# RasPi_Hat_Temp.net
KiCad netlist of a schematic drawn in Altium Designer
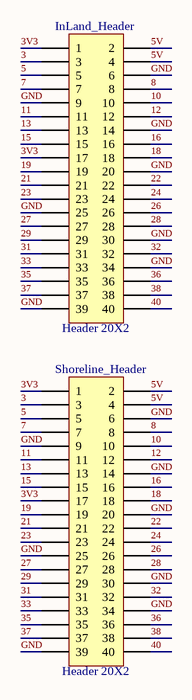
[diagram p0: RasPi_Hat_Temp.SchDoc]

(export (version "E")
  (design (tool "Eeschema 10.0.6"))
  (components
    (comp (ref "InLand_Header")
      (value "Header 20X2")
      (footprint "HDR2X20")
      (description "Header, 20-Pin, Dual row")
      (fields (field (name "PUBLISHER") "Altium Limited"))
      (libsource (lib "Miscellaneous Connectors") (part "Header 20X2"))
    )
    (comp (ref "Shoreline_Header")
      (value "Header 20X2")
      (footprint "HDR2X20")
      (description "Header, 20-Pin, Dual row")
      (fields (field (name "PUBLISHER") "Altium Limited"))
      (libsource (lib "Miscellaneous Connectors") (part "Header 20X2"))
    )
  )
  (nets
    (net (code "1") (name "/3") (class "Default")
      (node (ref "InLand_Header") (pin "3") (pinfunction "3_3") (pintype "passive"))
      (node (ref "Shoreline_Header") (pin "3") (pinfunction "3_3") (pintype "passive"))
    )
    (net (code "2") (name "/3V3") (class "Default")
      (node (ref "InLand_Header") (pin "1") (pinfunction "1_1") (pintype "passive"))
      (node (ref "InLand_Header") (pin "17") (pinfunction "17_17") (pintype "passive"))
      (node (ref "Shoreline_Header") (pin "1") (pinfunction "1_1") (pintype "passive"))
      (node (ref "Shoreline_Header") (pin "17") (pinfunction "17_17") (pintype "passive"))
    )
    (net (code "3") (name "/5") (class "Default")
      (node (ref "InLand_Header") (pin "5") (pinfunction "5_5") (pintype "passive"))
      (node (ref "Shoreline_Header") (pin "5") (pinfunction "5_5") (pintype "passive"))
    )
    (net (code "4") (name "/5V") (class "Default")
      (node (ref "InLand_Header") (pin "2") (pinfunction "2_2") (pintype "passive"))
      (node (ref "InLand_Header") (pin "4") (pinfunction "4_4") (pintype "passive"))
      (node (ref "Shoreline_Header") (pin "2") (pinfunction "2_2") (pintype "passive"))
      (node (ref "Shoreline_Header") (pin "4") (pinfunction "4_4") (pintype "passive"))
    )
    (net (code "5") (name "/7") (class "Default")
      (node (ref "InLand_Header") (pin "7") (pinfunction "7_7") (pintype "passive"))
      (node (ref "Shoreline_Header") (pin "7") (pinfunction "7_7") (pintype "passive"))
    )
    (net (code "6") (name "/8") (class "Default")
      (node (ref "InLand_Header") (pin "8") (pinfunction "8_8") (pintype "passive"))
      (node (ref "Shoreline_Header") (pin "8") (pinfunction "8_8") (pintype "passive"))
    )
    (net (code "7") (name "/10") (class "Default")
      (node (ref "InLand_Header") (pin "10") (pinfunction "10_10") (pintype "passive"))
      (node (ref "Shoreline_Header") (pin "10") (pinfunction "10_10") (pintype "passive"))
    )
    (net (code "8") (name "/11") (class "Default")
      (node (ref "InLand_Header") (pin "11") (pinfunction "11_11") (pintype "passive"))
      (node (ref "Shoreline_Header") (pin "11") (pinfunction "11_11") (pintype "passive"))
    )
    (net (code "9") (name "/12") (class "Default")
      (node (ref "InLand_Header") (pin "12") (pinfunction "12_12") (pintype "passive"))
      (node (ref "Shoreline_Header") (pin "12") (pinfunction "12_12") (pintype "passive"))
    )
    (net (code "10") (name "/13") (class "Default")
      (node (ref "InLand_Header") (pin "13") (pinfunction "13_13") (pintype "passive"))
      (node (ref "Shoreline_Header") (pin "13") (pinfunction "13_13") (pintype "passive"))
    )
    (net (code "11") (name "/15") (class "Default")
      (node (ref "InLand_Header") (pin "15") (pinfunction "15_15") (pintype "passive"))
      (node (ref "Shoreline_Header") (pin "15") (pinfunction "15_15") (pintype "passive"))
    )
    (net (code "12") (name "/16") (class "Default")
      (node (ref "InLand_Header") (pin "16") (pinfunction "16_16") (pintype "passive"))
      (node (ref "Shoreline_Header") (pin "16") (pinfunction "16_16") (pintype "passive"))
    )
    (net (code "13") (name "/18") (class "Default")
      (node (ref "InLand_Header") (pin "18") (pinfunction "18_18") (pintype "passive"))
      (node (ref "Shoreline_Header") (pin "18") (pinfunction "18_18") (pintype "passive"))
    )
    (net (code "14") (name "/19") (class "Default")
      (node (ref "InLand_Header") (pin "19") (pinfunction "19_19") (pintype "passive"))
      (node (ref "Shoreline_Header") (pin "19") (pinfunction "19_19") (pintype "passive"))
    )
    (net (code "15") (name "/21") (class "Default")
      (node (ref "InLand_Header") (pin "21") (pinfunction "21_21") (pintype "passive"))
      (node (ref "Shoreline_Header") (pin "21") (pinfunction "21_21") (pintype "passive"))
    )
    (net (code "16") (name "/22") (class "Default")
      (node (ref "InLand_Header") (pin "22") (pinfunction "22_22") (pintype "passive"))
      (node (ref "Shoreline_Header") (pin "22") (pinfunction "22_22") (pintype "passive"))
    )
    (net (code "17") (name "/23") (class "Default")
      (node (ref "InLand_Header") (pin "23") (pinfunction "23_23") (pintype "passive"))
      (node (ref "Shoreline_Header") (pin "23") (pinfunction "23_23") (pintype "passive"))
    )
    (net (code "18") (name "/24") (class "Default")
      (node (ref "InLand_Header") (pin "24") (pinfunction "24_24") (pintype "passive"))
      (node (ref "Shoreline_Header") (pin "24") (pinfunction "24_24") (pintype "passive"))
    )
    (net (code "19") (name "/26") (class "Default")
      (node (ref "InLand_Header") (pin "26") (pinfunction "26_26") (pintype "passive"))
      (node (ref "Shoreline_Header") (pin "26") (pinfunction "26_26") (pintype "passive"))
    )
    (net (code "20") (name "/27") (class "Default")
      (node (ref "InLand_Header") (pin "27") (pinfunction "27_27") (pintype "passive"))
      (node (ref "Shoreline_Header") (pin "27") (pinfunction "27_27") (pintype "passive"))
    )
    (net (code "21") (name "/28") (class "Default")
      (node (ref "InLand_Header") (pin "28") (pinfunction "28_28") (pintype "passive"))
      (node (ref "Shoreline_Header") (pin "28") (pinfunction "28_28") (pintype "passive"))
    )
    (net (code "22") (name "/29") (class "Default")
      (node (ref "InLand_Header") (pin "29") (pinfunction "29_29") (pintype "passive"))
      (node (ref "Shoreline_Header") (pin "29") (pinfunction "29_29") (pintype "passive"))
    )
    (net (code "23") (name "/31") (class "Default")
      (node (ref "InLand_Header") (pin "31") (pinfunction "31_31") (pintype "passive"))
      (node (ref "Shoreline_Header") (pin "31") (pinfunction "31_31") (pintype "passive"))
    )
    (net (code "24") (name "/32") (class "Default")
      (node (ref "InLand_Header") (pin "32") (pinfunction "32_32") (pintype "passive"))
      (node (ref "Shoreline_Header") (pin "32") (pinfunction "32_32") (pintype "passive"))
    )
    (net (code "25") (name "/33") (class "Default")
      (node (ref "InLand_Header") (pin "33") (pinfunction "33_33") (pintype "passive"))
      (node (ref "Shoreline_Header") (pin "33") (pinfunction "33_33") (pintype "passive"))
    )
    (net (code "26") (name "/35") (class "Default")
      (node (ref "InLand_Header") (pin "35") (pinfunction "35_35") (pintype "passive"))
      (node (ref "Shoreline_Header") (pin "35") (pinfunction "35_35") (pintype "passive"))
    )
    (net (code "27") (name "/36") (class "Default")
      (node (ref "InLand_Header") (pin "36") (pinfunction "36_36") (pintype "passive"))
      (node (ref "Shoreline_Header") (pin "36") (pinfunction "36_36") (pintype "passive"))
    )
    (net (code "28") (name "/37") (class "Default")
      (node (ref "InLand_Header") (pin "37") (pinfunction "37_37") (pintype "passive"))
      (node (ref "Shoreline_Header") (pin "37") (pinfunction "37_37") (pintype "passive"))
    )
    (net (code "29") (name "/38") (class "Default")
      (node (ref "InLand_Header") (pin "38") (pinfunction "38_38") (pintype "passive"))
      (node (ref "Shoreline_Header") (pin "38") (pinfunction "38_38") (pintype "passive"))
    )
    (net (code "30") (name "/40") (class "Default")
      (node (ref "InLand_Header") (pin "40") (pinfunction "40_40") (pintype "passive"))
      (node (ref "Shoreline_Header") (pin "40") (pinfunction "40_40") (pintype "passive"))
    )
    (net (code "31") (name "/GND") (class "Default")
      (node (ref "InLand_Header") (pin "14") (pinfunction "14_14") (pintype "passive"))
      (node (ref "InLand_Header") (pin "20") (pinfunction "20_20") (pintype "passive"))
      (node (ref "InLand_Header") (pin "25") (pinfunction "25_25") (pintype "passive"))
      (node (ref "InLand_Header") (pin "30") (pinfunction "30_30") (pintype "passive"))
      (node (ref "InLand_Header") (pin "34") (pinfunction "34_34") (pintype "passive"))
      (node (ref "InLand_Header") (pin "39") (pinfunction "39_39") (pintype "passive"))
      (node (ref "InLand_Header") (pin "6") (pinfunction "6_6") (pintype "passive"))
      (node (ref "InLand_Header") (pin "9") (pinfunction "9_9") (pintype "passive"))
      (node (ref "Shoreline_Header") (pin "14") (pinfunction "14_14") (pintype "passive"))
      (node (ref "Shoreline_Header") (pin "20") (pinfunction "20_20") (pintype "passive"))
      (node (ref "Shoreline_Header") (pin "25") (pinfunction "25_25") (pintype "passive"))
      (node (ref "Shoreline_Header") (pin "30") (pinfunction "30_30") (pintype "passive"))
      (node (ref "Shoreline_Header") (pin "34") (pinfunction "34_34") (pintype "passive"))
      (node (ref "Shoreline_Header") (pin "39") (pinfunction "39_39") (pintype "passive"))
      (node (ref "Shoreline_Header") (pin "6") (pinfunction "6_6") (pintype "passive"))
      (node (ref "Shoreline_Header") (pin "9") (pinfunction "9_9") (pintype "passive"))
    )
  )
)
